# USB-JTAG-Programmer_v4_0.net
KiCad netlist of a schematic drawn in EAGLE
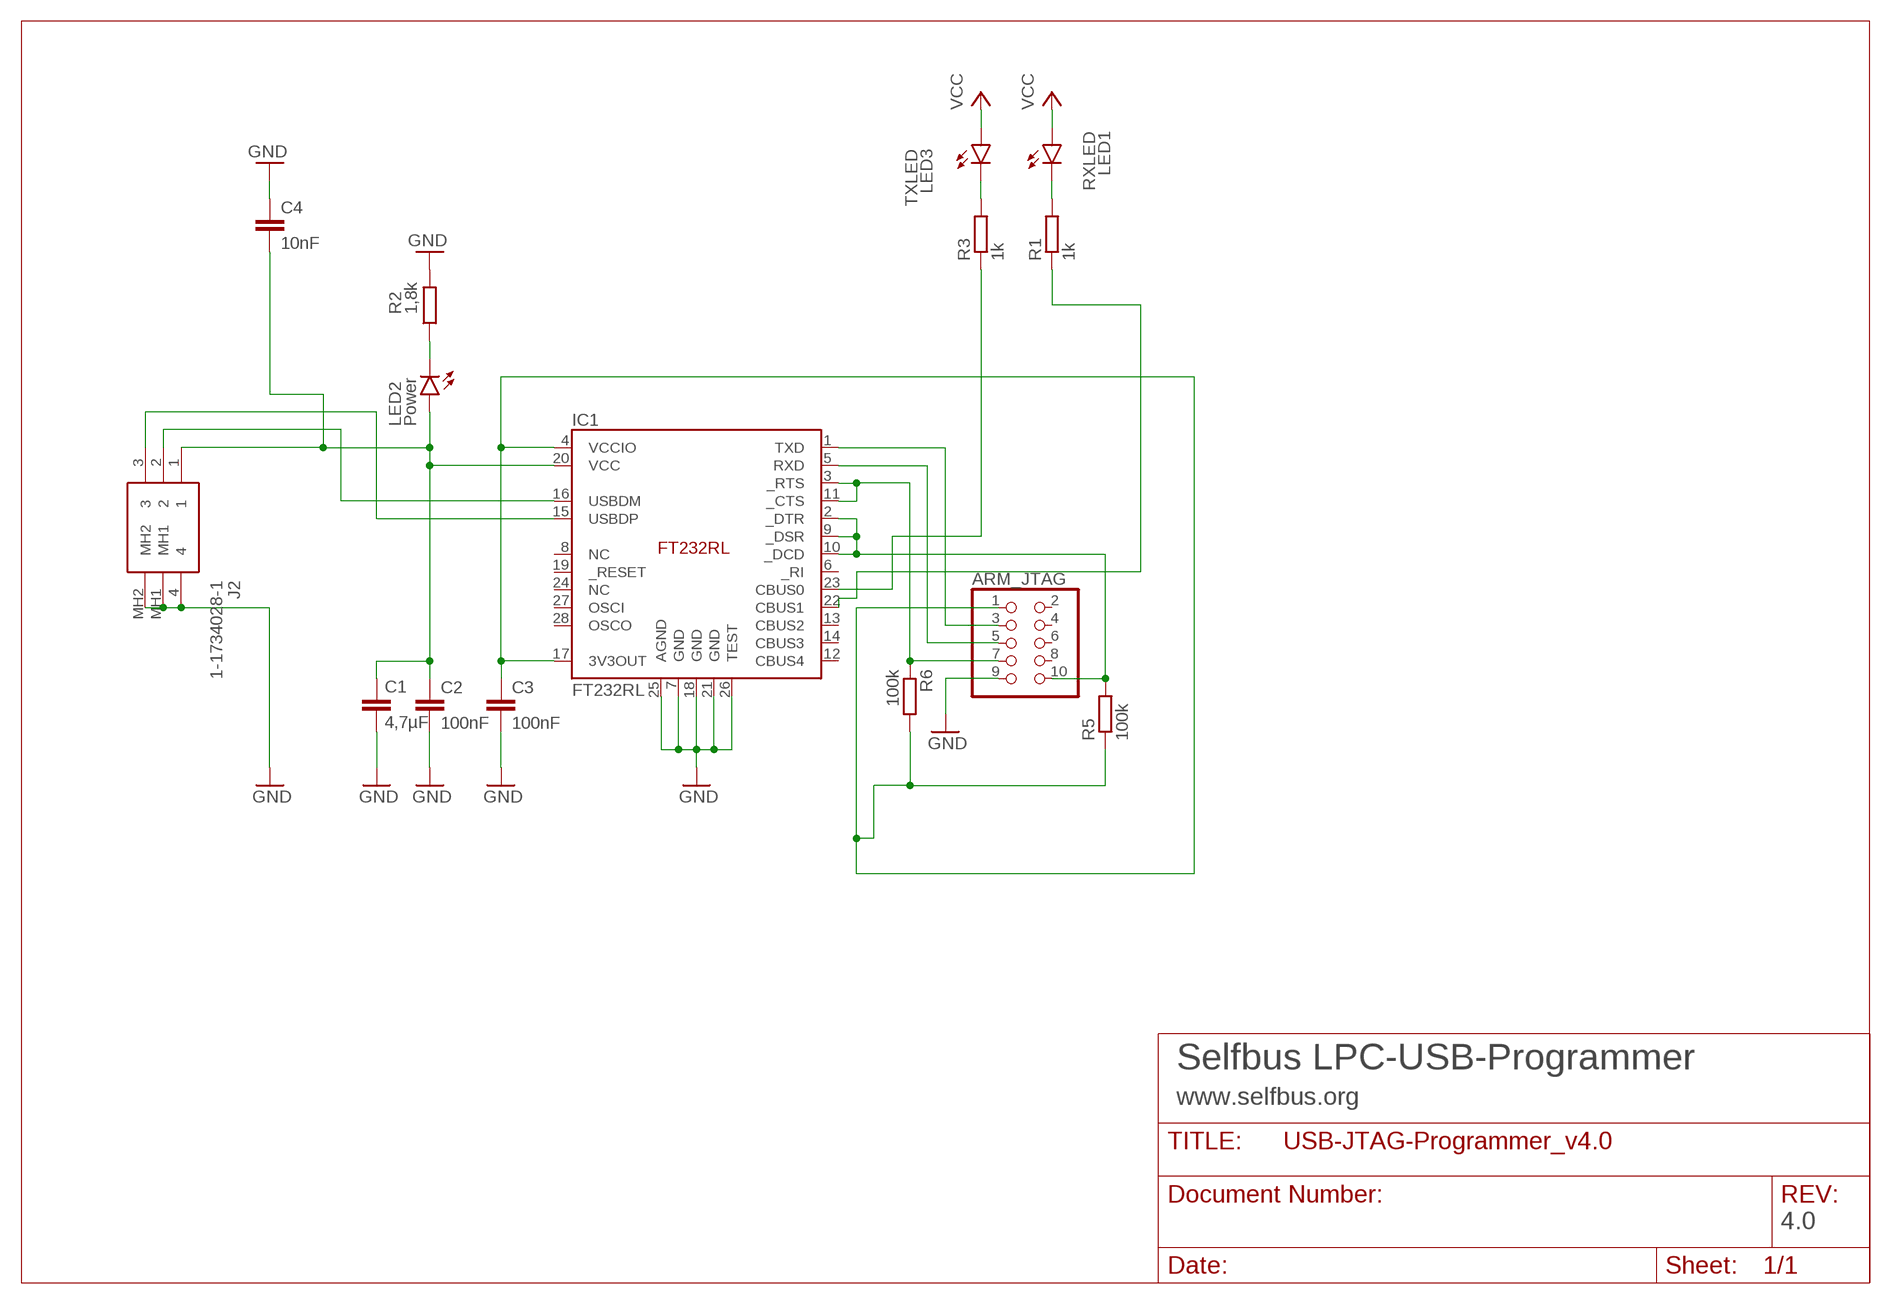
[diagram p0: schematic, sheet 1]

(export (version "E")
  (design (tool "Eeschema 10.0.6"))
  (components
    (comp (ref "ARM_JTAG")
      (value "PINHD-2X5_2.00")
      (footprint "eagle-import:2X05M")
      (libsource (lib "eagle-import") (part "PINHD-2X5_2.00"))
    )
    (comp (ref "C1")
      (value "4,7µF")
      (footprint "eagle-import:C1206K")
      (libsource (lib "eagle-import") (part "C-EUC1206K"))
    )
    (comp (ref "C2")
      (value "100nF")
      (footprint "eagle-import:C0805K")
      (libsource (lib "eagle-import") (part "C-EUC0805K"))
    )
    (comp (ref "C3")
      (value "100nF")
      (footprint "eagle-import:C0805K")
      (libsource (lib "eagle-import") (part "C-EUC0805K"))
    )
    (comp (ref "C4")
      (value "10nF")
      (footprint "eagle-import:C0805K")
      (libsource (lib "eagle-import") (part "C-EUC0805K"))
    )
    (comp (ref "IC1")
      (value "FT232RL")
      (footprint "eagle-import:SSOP-28")
      (libsource (lib "eagle-import") (part "FT232RL"))
    )
    (comp (ref "J2")
      (value "1-1734028-1")
      (footprint "eagle-import:117340281")
      (fields (field (name "MOUSER_PART_NUMBER") "571-1-1734028-1"))
      (libsource (lib "eagle-import") (part "1-1734028-1"))
    )
    (comp (ref "LED1")
      (value "RXLED")
      (footprint "eagle-import:CHIPLED_0805")
      (libsource (lib "eagle-import") (part "LEDCHIPLED_0805"))
    )
    (comp (ref "LED2")
      (value "Power")
      (footprint "eagle-import:CHIPLED_0805")
      (libsource (lib "eagle-import") (part "LEDCHIPLED_0805"))
    )
    (comp (ref "LED3")
      (value "TXLED")
      (footprint "eagle-import:CHIPLED_0805")
      (libsource (lib "eagle-import") (part "LEDCHIPLED_0805"))
    )
    (comp (ref "R1")
      (value "1k")
      (footprint "eagle-import:R0805")
      (libsource (lib "eagle-import") (part "resistor_348_R-EU_R0805"))
    )
    (comp (ref "R2")
      (value "1,8k")
      (footprint "eagle-import:R0805")
      (libsource (lib "eagle-import") (part "R-EU_R0805"))
    )
    (comp (ref "R3")
      (value "1k")
      (footprint "eagle-import:R0805")
      (libsource (lib "eagle-import") (part "resistor_348_R-EU_R0805"))
    )
    (comp (ref "R5")
      (value "100k")
      (footprint "eagle-import:R0805")
      (libsource (lib "eagle-import") (part "resistor_348_R-EU_R0805"))
    )
    (comp (ref "R6")
      (value "100k")
      (footprint "eagle-import:R0805")
      (libsource (lib "eagle-import") (part "R-EU_R0805"))
    )
  )
  (nets
    (net (code "1") (name "GND") (class "Default")
      (node (ref "ARM_JTAG") (pin "9") (pinfunction "9_9") (pintype "passive"))
      (node (ref "C1") (pin "2") (pinfunction "2_2") (pintype "passive"))
      (node (ref "C2") (pin "2") (pinfunction "2_2") (pintype "passive"))
      (node (ref "C3") (pin "2") (pinfunction "2_2") (pintype "passive"))
      (node (ref "C4") (pin "1") (pinfunction "1_1") (pintype "passive"))
      (node (ref "IC1") (pin "18") (pinfunction "GND_18") (pintype "power_in"))
      (node (ref "IC1") (pin "21") (pinfunction "GND_21") (pintype "power_in"))
      (node (ref "IC1") (pin "25") (pinfunction "AGND_25") (pintype "power_in"))
      (node (ref "IC1") (pin "26") (pinfunction "TEST_26") (pintype "bidirectional"))
      (node (ref "IC1") (pin "7") (pinfunction "GND_7") (pintype "power_in"))
      (node (ref "J2") (pin "4") (pinfunction "4_4") (pintype "bidirectional"))
      (node (ref "J2") (pin "MH1") (pinfunction "MH1_MH1") (pintype "bidirectional"))
      (node (ref "J2") (pin "MH2") (pinfunction "MH2_MH2") (pintype "bidirectional"))
      (node (ref "R2") (pin "2") (pinfunction "2_2") (pintype "passive"))
    )
    (net (code "2") (name "Net-(IC1-3V3OUT)") (class "Default")
      (node (ref "ARM_JTAG") (pin "1") (pinfunction "1_1") (pintype "passive"))
      (node (ref "C3") (pin "1") (pinfunction "1_1") (pintype "passive"))
      (node (ref "IC1") (pin "17") (pinfunction "3V3OUT_17") (pintype "output"))
      (node (ref "IC1") (pin "4") (pinfunction "VCCIO_4") (pintype "power_in"))
      (node (ref "R5") (pin "1") (pinfunction "1_1") (pintype "passive"))
      (node (ref "R6") (pin "2") (pinfunction "2_2") (pintype "passive"))
    )
    (net (code "3") (name "Net-(IC1-CBUS0)") (class "Default")
      (node (ref "IC1") (pin "23") (pinfunction "CBUS0_23") (pintype "bidirectional"))
      (node (ref "R3") (pin "1") (pinfunction "1_1") (pintype "passive"))
    )
    (net (code "4") (name "Net-(IC1-CBUS1)") (class "Default")
      (node (ref "IC1") (pin "22") (pinfunction "CBUS1_22") (pintype "bidirectional"))
      (node (ref "R1") (pin "1") (pinfunction "1_1") (pintype "passive"))
    )
    (net (code "5") (name "Net-(IC1-RXD)") (class "Default")
      (node (ref "ARM_JTAG") (pin "5") (pinfunction "5_5") (pintype "passive"))
      (node (ref "IC1") (pin "5") (pinfunction "RXD_5") (pintype "input"))
    )
    (net (code "6") (name "Net-(IC1-TXD)") (class "Default")
      (node (ref "ARM_JTAG") (pin "3") (pinfunction "3_3") (pintype "passive"))
      (node (ref "IC1") (pin "1") (pinfunction "TXD_1") (pintype "output"))
    )
    (net (code "7") (name "Net-(IC1-USBDM)") (class "Default")
      (node (ref "IC1") (pin "16") (pinfunction "USBDM_16") (pintype "bidirectional"))
      (node (ref "J2") (pin "2") (pinfunction "2_2") (pintype "bidirectional"))
    )
    (net (code "8") (name "Net-(IC1-USBDP)") (class "Default")
      (node (ref "IC1") (pin "15") (pinfunction "USBDP_15") (pintype "bidirectional"))
      (node (ref "J2") (pin "3") (pinfunction "3_3") (pintype "bidirectional"))
    )
    (net (code "9") (name "Net-(IC1-_CTS)") (class "Default")
      (node (ref "ARM_JTAG") (pin "7") (pinfunction "7_7") (pintype "passive"))
      (node (ref "IC1") (pin "11") (pinfunction "_CTS_11") (pintype "input"))
      (node (ref "IC1") (pin "3") (pinfunction "_RTS_3") (pintype "output"))
      (node (ref "R6") (pin "1") (pinfunction "1_1") (pintype "passive"))
    )
    (net (code "10") (name "Net-(IC1-_DCD)") (class "Default")
      (node (ref "ARM_JTAG") (pin "10") (pinfunction "10_10") (pintype "passive"))
      (node (ref "IC1") (pin "10") (pinfunction "_DCD_10") (pintype "input"))
      (node (ref "IC1") (pin "2") (pinfunction "_DTR_2") (pintype "input"))
      (node (ref "IC1") (pin "9") (pinfunction "_DSR_9") (pintype "input"))
      (node (ref "R5") (pin "2") (pinfunction "2_2") (pintype "passive"))
    )
    (net (code "11") (name "Net-(LED1-PadC)") (class "Default")
      (node (ref "LED1") (pin "C") (pinfunction "C_C") (pintype "passive"))
      (node (ref "R1") (pin "2") (pinfunction "2_2") (pintype "passive"))
    )
    (net (code "12") (name "Net-(LED2-PadC)") (class "Default")
      (node (ref "LED2") (pin "C") (pinfunction "C_C") (pintype "passive"))
      (node (ref "R2") (pin "1") (pinfunction "1_1") (pintype "passive"))
    )
    (net (code "13") (name "Net-(LED3-PadC)") (class "Default")
      (node (ref "LED3") (pin "C") (pinfunction "C_C") (pintype "passive"))
      (node (ref "R3") (pin "2") (pinfunction "2_2") (pintype "passive"))
    )
    (net (code "14") (name "VCC") (class "Default")
      (node (ref "C1") (pin "1") (pinfunction "1_1") (pintype "passive"))
      (node (ref "C2") (pin "1") (pinfunction "1_1") (pintype "passive"))
      (node (ref "C4") (pin "2") (pinfunction "2_2") (pintype "passive"))
      (node (ref "IC1") (pin "20") (pinfunction "VCC_20") (pintype "power_in"))
      (node (ref "J2") (pin "1") (pinfunction "1_1") (pintype "bidirectional"))
      (node (ref "LED1") (pin "A") (pinfunction "A_A") (pintype "passive"))
      (node (ref "LED2") (pin "A") (pinfunction "A_A") (pintype "passive"))
      (node (ref "LED3") (pin "A") (pinfunction "A_A") (pintype "passive"))
    )
    (net (code "15") (name "unconnected-(ARM_JTAG-Pad2)") (class "Default")
      (node (ref "ARM_JTAG") (pin "2") (pinfunction "2_2") (pintype "passive"))
    )
    (net (code "16") (name "unconnected-(ARM_JTAG-Pad4)") (class "Default")
      (node (ref "ARM_JTAG") (pin "4") (pinfunction "4_4") (pintype "passive"))
    )
    (net (code "17") (name "unconnected-(ARM_JTAG-Pad6)") (class "Default")
      (node (ref "ARM_JTAG") (pin "6") (pinfunction "6_6") (pintype "passive"))
    )
    (net (code "18") (name "unconnected-(ARM_JTAG-Pad8)") (class "Default")
      (node (ref "ARM_JTAG") (pin "8") (pinfunction "8_8") (pintype "passive"))
    )
    (net (code "19") (name "unconnected-(IC1-CBUS2-Pad13)") (class "Default")
      (node (ref "IC1") (pin "13") (pinfunction "CBUS2_13") (pintype "bidirectional"))
    )
    (net (code "20") (name "unconnected-(IC1-CBUS3-Pad14)") (class "Default")
      (node (ref "IC1") (pin "14") (pinfunction "CBUS3_14") (pintype "bidirectional"))
    )
    (net (code "21") (name "unconnected-(IC1-CBUS4-Pad12)") (class "Default")
      (node (ref "IC1") (pin "12") (pinfunction "CBUS4_12") (pintype "bidirectional"))
    )
    (net (code "22") (name "unconnected-(IC1-NC-Pad8)") (class "Default")
      (node (ref "IC1") (pin "8") (pinfunction "NC_8") (pintype "no_connect"))
    )
    (net (code "23") (name "unconnected-(IC1-NC-Pad24)") (class "Default")
      (node (ref "IC1") (pin "24") (pinfunction "NC_24") (pintype "no_connect"))
    )
    (net (code "24") (name "unconnected-(IC1-OSCI-Pad27)") (class "Default")
      (node (ref "IC1") (pin "27") (pinfunction "OSCI_27") (pintype "input"))
    )
    (net (code "25") (name "unconnected-(IC1-OSCO-Pad28)") (class "Default")
      (node (ref "IC1") (pin "28") (pinfunction "OSCO_28") (pintype "output"))
    )
    (net (code "26") (name "unconnected-(IC1-_RESET-Pad19)") (class "Default")
      (node (ref "IC1") (pin "19") (pinfunction "_RESET_19") (pintype "input"))
    )
    (net (code "27") (name "unconnected-(IC1-_RI-Pad6)") (class "Default")
      (node (ref "IC1") (pin "6") (pinfunction "_RI_6") (pintype "input"))
    )
  )
)
